# 02_-_MICROCONTROLADOR.net
KiCad netlist of a schematic drawn in Altium Designer
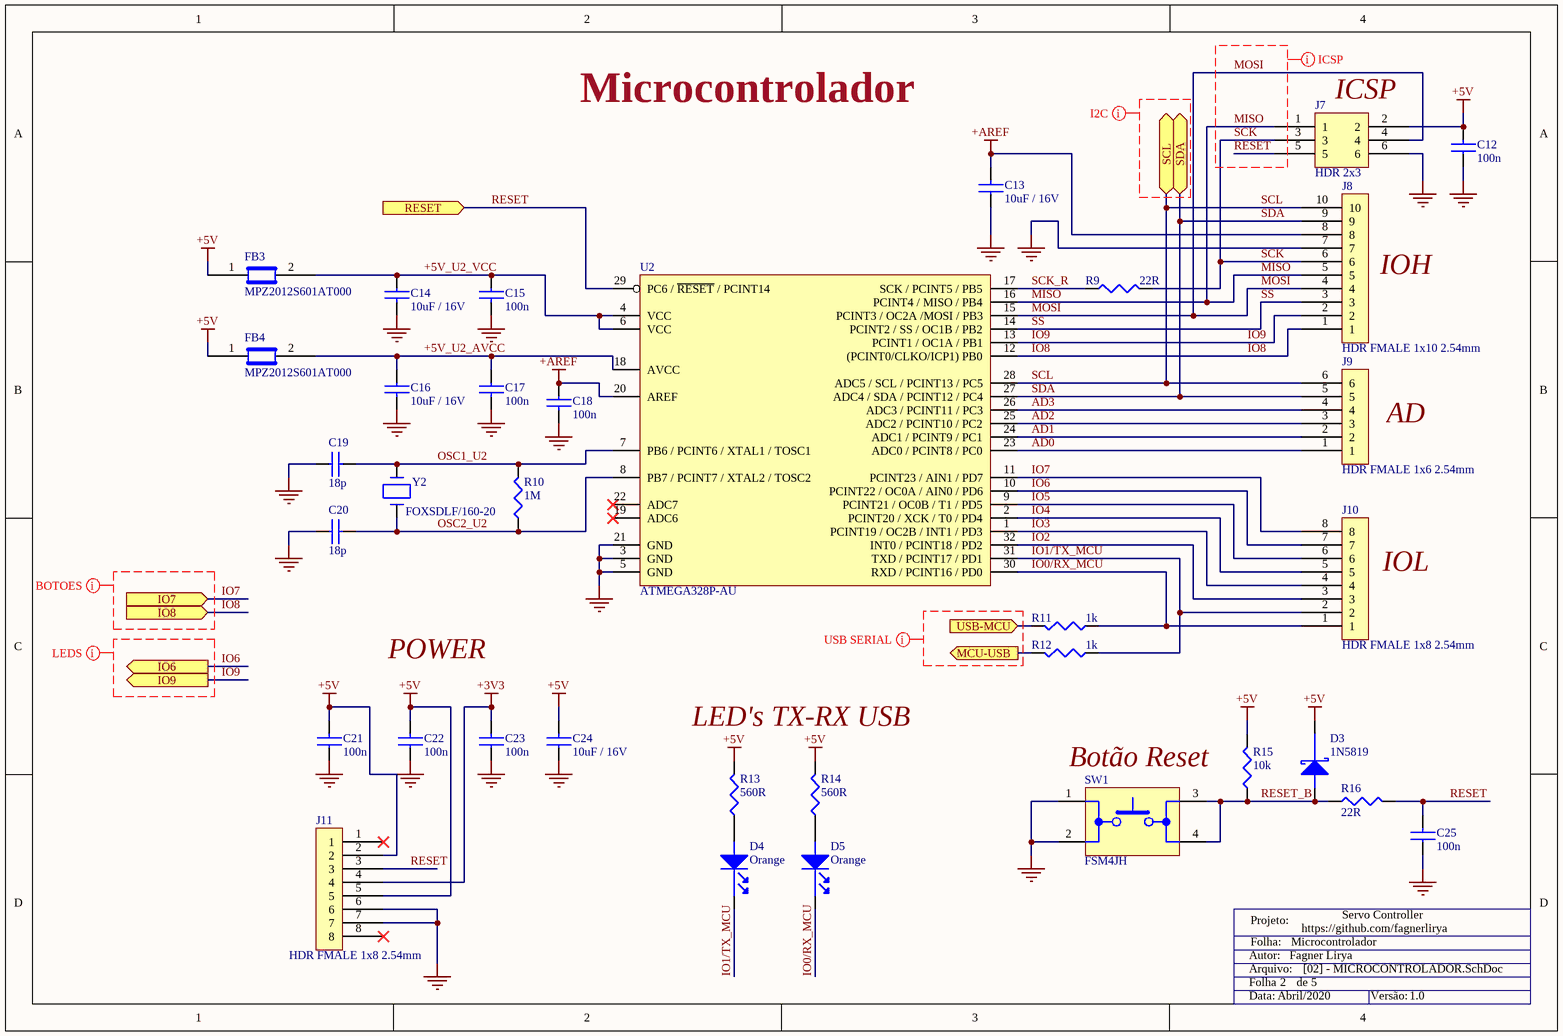
[diagram p0: [02] - MICROCONTROLADOR.SchDoc]

(export (version "E")
  (design (tool "Eeschema 10.0.6"))
  (components
    (comp (ref "C12")
      (value "100n")
      (footprint "C0805")
      (description "CAP CER 0.1UF 50V X7R 0805")
      (fields
        (field (name "MANUFACTURER") "TDK Corporation")
        (field (name "MANUFACTURER PART NUMBER") "C2012X7R1H104K085AA")
      )
      (libsource (lib "Servo_Control_Lib") (part "C2012X7R1H104K085AA_1"))
    )
    (comp (ref "C13")
      (value "10uF / 16V")
      (footprint "C0805")
      (description "CAP CER 10UF 16V X5R 0805")
      (fields
        (field (name "MANUFACTURER") "TDK Corporation")
        (field (name "MANUFACTURER PART NUMBER") "C2012X5R1C106M125AC")
      )
      (libsource (lib "Servo_Control_Lib") (part "C2012X5R1C106M125AC"))
    )
    (comp (ref "C14")
      (value "10uF / 16V")
      (footprint "C0805")
      (description "CAP CER 10UF 16V X5R 0805")
      (fields
        (field (name "MANUFACTURER") "TDK Corporation")
        (field (name "MANUFACTURER PART NUMBER") "C2012X5R1C106M125AC")
      )
      (libsource (lib "Servo_Control_Lib") (part "C2012X5R1C106M125AC"))
    )
    (comp (ref "C15")
      (value "100n")
      (footprint "C0805")
      (description "CAP CER 0.1UF 50V X7R 0805")
      (fields
        (field (name "MANUFACTURER") "TDK Corporation")
        (field (name "MANUFACTURER PART NUMBER") "C2012X7R1H104K085AA")
      )
      (libsource (lib "Servo_Control_Lib") (part "C2012X7R1H104K085AA_1"))
    )
    (comp (ref "C16")
      (value "10uF / 16V")
      (footprint "C0805")
      (description "CAP CER 10UF 16V X5R 0805")
      (fields
        (field (name "MANUFACTURER") "TDK Corporation")
        (field (name "MANUFACTURER PART NUMBER") "C2012X5R1C106M125AC")
      )
      (libsource (lib "Servo_Control_Lib") (part "C2012X5R1C106M125AC"))
    )
    (comp (ref "C17")
      (value "100n")
      (footprint "C0805")
      (description "CAP CER 0.1UF 50V X7R 0805")
      (fields
        (field (name "MANUFACTURER") "TDK Corporation")
        (field (name "MANUFACTURER PART NUMBER") "C2012X7R1H104K085AA")
      )
      (libsource (lib "Servo_Control_Lib") (part "C2012X7R1H104K085AA_1"))
    )
    (comp (ref "C18")
      (value "100n")
      (footprint "C0805")
      (description "CAP CER 0.1UF 50V X7R 0805")
      (fields
        (field (name "MANUFACTURER") "TDK Corporation")
        (field (name "MANUFACTURER PART NUMBER") "C2012X7R1H104K085AA")
      )
      (libsource (lib "Servo_Control_Lib") (part "C2012X7R1H104K085AA_1"))
    )
    (comp (ref "C19")
      (value "18p")
      (footprint "C0805")
      (description "CAP CER 18PF 50V NP0 0805")
      (fields
        (field (name "MANUFACTURER") "Kemet")
        (field (name "MANUFACTURER PART NUMBER") "C0805C180J5GACTU")
      )
      (libsource (lib "Servo_Control_Lib") (part "C0805C180J5GACTU"))
    )
    (comp (ref "C20")
      (value "18p")
      (footprint "C0805")
      (description "CAP CER 18PF 50V NP0 0805")
      (fields
        (field (name "MANUFACTURER") "Kemet")
        (field (name "MANUFACTURER PART NUMBER") "C0805C180J5GACTU")
      )
      (libsource (lib "Servo_Control_Lib") (part "C0805C180J5GACTU"))
    )
    (comp (ref "C21")
      (value "100n")
      (footprint "C0805")
      (description "CAP CER 0.1UF 50V X7R 0805")
      (fields
        (field (name "MANUFACTURER") "TDK Corporation")
        (field (name "MANUFACTURER PART NUMBER") "C2012X7R1H104K085AA")
      )
      (libsource (lib "Servo_Control_Lib") (part "C2012X7R1H104K085AA_1"))
    )
    (comp (ref "C22")
      (value "100n")
      (footprint "C0805")
      (description "CAP CER 0.1UF 50V X7R 0805")
      (fields
        (field (name "MANUFACTURER") "TDK Corporation")
        (field (name "MANUFACTURER PART NUMBER") "C2012X7R1H104K085AA")
      )
      (libsource (lib "Servo_Control_Lib") (part "C2012X7R1H104K085AA_1"))
    )
    (comp (ref "C23")
      (value "100n")
      (footprint "C0805")
      (description "CAP CER 0.1UF 50V X7R 0805")
      (fields
        (field (name "MANUFACTURER") "TDK Corporation")
        (field (name "MANUFACTURER PART NUMBER") "C2012X7R1H104K085AA")
      )
      (libsource (lib "Servo_Control_Lib") (part "C2012X7R1H104K085AA_1"))
    )
    (comp (ref "C24")
      (value "10uF / 16V")
      (footprint "C0805")
      (description "CAP CER 10UF 16V X5R 0805")
      (fields
        (field (name "MANUFACTURER") "TDK Corporation")
        (field (name "MANUFACTURER PART NUMBER") "C2012X5R1C106M125AC")
      )
      (libsource (lib "Servo_Control_Lib") (part "C2012X5R1C106M125AC"))
    )
    (comp (ref "C25")
      (value "100n")
      (footprint "C0805")
      (description "CAP CER 0.1UF 50V X7R 0805")
      (fields
        (field (name "MANUFACTURER") "TDK Corporation")
        (field (name "MANUFACTURER PART NUMBER") "C2012X7R1H104K085AA")
      )
      (libsource (lib "Servo_Control_Lib") (part "C2012X7R1H104K085AA_1"))
    )
    (comp (ref "D3")
      (value "1N5819")
      (footprint "1N5819")
      (description "Schottky Diodes & Rectifiers Schottky Barrier")
      (fields (field (name "MANUFACTURER") "ON Semiconductor / Fairchild"))
      (libsource (lib "Servo_Control_Lib") (part "1N5819"))
    )
    (comp (ref "D4")
      (value "Orange")
      (footprint "LED_0603")
      (description "LED ORANGE DIFFUSED 0603 SMD")
      (fields
        (field (name "MANUFACTURER") "OSRAM Opto Semiconductors Inc.")
        (field (name "MANUFACTURER PART NUMBER") "LO L29K-H2K1-24-Z")
      )
      (libsource (lib "Servo_Control_Lib") (part "LO L29K-H2K1-24-Z"))
    )
    (comp (ref "D5")
      (value "Orange")
      (footprint "LED_0603")
      (description "LED ORANGE DIFFUSED 0603 SMD")
      (fields
        (field (name "MANUFACTURER") "OSRAM Opto Semiconductors Inc.")
        (field (name "MANUFACTURER PART NUMBER") "LO L29K-H2K1-24-Z")
      )
      (libsource (lib "Servo_Control_Lib") (part "LO L29K-H2K1-24-Z"))
    )
    (comp (ref "FB3")
      (value "MPZ2012S601AT000")
      (footprint "C0805")
      (description "FERRITE CHIP BEAD 600 OHM SMD")
      (fields (field (name "MANUFACTURER") "TDK Corporation"))
      (libsource (lib "Servo_Control_Lib") (part "MPZ2012S601AT000"))
    )
    (comp (ref "FB4")
      (value "MPZ2012S601AT000")
      (footprint "C0805")
      (description "FERRITE CHIP BEAD 600 OHM SMD")
      (fields (field (name "MANUFACTURER") "TDK Corporation"))
      (libsource (lib "Servo_Control_Lib") (part "MPZ2012S601AT000"))
    )
    (comp (ref "J7")
      (value "HDR 2x3")
      (footprint "HDR_2x3_2.54MM")
      (description "CONN HEADER 6POS .100 STR 30AU")
      (fields (field (name "MANUFACTURER") "FCI") (field (name "MANUFACTURER PART NUMBER") "67997-106HLF"))
      (libsource (lib "Servo_Control_Lib") (part "67997-106HLF"))
    )
    (comp (ref "J8")
      (value "HDR FMALE 1x10 2.54mm")
      (footprint "Hdr_Female_1x10_2.54mm")
      (description "10-WAY SIL VERT SOCKET L/FREE")
      (fields
        (field (name "MANUFACTURER") "Harwin Inc.")
        (field (name "MANUFACTURER PART NUMBER") "M20-7821046")
      )
      (libsource (lib "Servo_Control_Lib") (part "M20-7821046"))
    )
    (comp (ref "J9")
      (value "HDR FMALE 1x6 2.54mm")
      (footprint "Hdr_Female_1x6_2.54mm")
      (description "06-WAY SIL VERT SOCKET L/FREE")
      (fields
        (field (name "MANUFACTURER") "Harwin Inc.")
        (field (name "MANUFACTURER PART NUMBER") "M20-7820646")
      )
      (libsource (lib "Servo_Control_Lib") (part "M20-7820646"))
    )
    (comp (ref "J10")
      (value "HDR FMALE 1x8 2.54mm")
      (footprint "Hdr_Female_1x8_2.54mm")
      (description "08-WAY SIL VERT SOCKET L/FREE")
      (fields
        (field (name "MANUFACTURER") "Harwin Inc.")
        (field (name "MANUFACTURER PART NUMBER") "M20-7820842")
      )
      (libsource (lib "Servo_Control_Lib") (part "M20-7820842"))
    )
    (comp (ref "J11")
      (value "HDR FMALE 1x8 2.54mm")
      (footprint "Hdr_Female_1x8_2.54mm")
      (description "08-WAY SIL VERT SOCKET L/FREE")
      (fields
        (field (name "MANUFACTURER") "Harwin Inc.")
        (field (name "MANUFACTURER PART NUMBER") "M20-7820842")
      )
      (libsource (lib "") (part "M20-7820842_1"))
    )
    (comp (ref "R9")
      (value "22R")
      (footprint "R0805")
      (description "RES SMD 22 OHM 1% 1/8W 0805")
      (fields
        (field (name "MANUFACTURER") "Yageo")
        (field (name "MANUFACTURER PART NUMBER") "RC0805FR-0722RL")
      )
      (libsource (lib "Servo_Control_Lib") (part "RC0805FR-0722RL"))
    )
    (comp (ref "R10")
      (value "1M")
      (footprint "R0805")
      (description "RES SMD 1M OHM 1% 1/8W 0805")
      (fields
        (field (name "MANUFACTURER") "Yageo")
        (field (name "MANUFACTURER PART NUMBER") "RC0805FR-071ML")
      )
      (libsource (lib "Servo_Control_Lib") (part "RC0805FR-071ML"))
    )
    (comp (ref "R11")
      (value "1k")
      (footprint "R0805")
      (description "RES SMD 1K OHM 1% 1/8W 0805")
      (fields
        (field (name "MANUFACTURER") "Yageo")
        (field (name "MANUFACTURER PART NUMBER") "RC0805FR-071KL")
      )
      (libsource (lib "Servo_Control_Lib") (part "RC0805FR-071KL"))
    )
    (comp (ref "R12")
      (value "1k")
      (footprint "R0805")
      (description "RES SMD 1K OHM 1% 1/8W 0805")
      (fields
        (field (name "MANUFACTURER") "Yageo")
        (field (name "MANUFACTURER PART NUMBER") "RC0805FR-071KL")
      )
      (libsource (lib "Servo_Control_Lib") (part "RC0805FR-071KL"))
    )
    (comp (ref "R13")
      (value "560R")
      (footprint "R0805")
      (description "RES SMD 560 OHM 1% 1/8W 0805")
      (fields
        (field (name "MANUFACTURER") "Yageo")
        (field (name "MANUFACTURER PART NUMBER") "RC0805FR-07560RL")
      )
      (libsource (lib "Servo_Control_Lib") (part "RC0805FR-07560RL"))
    )
    (comp (ref "R14")
      (value "560R")
      (footprint "R0805")
      (description "RES SMD 560 OHM 1% 1/8W 0805")
      (fields
        (field (name "MANUFACTURER") "Yageo")
        (field (name "MANUFACTURER PART NUMBER") "RC0805FR-07560RL")
      )
      (libsource (lib "Servo_Control_Lib") (part "RC0805FR-07560RL"))
    )
    (comp (ref "R15")
      (value "10k")
      (footprint "R0805")
      (description "RES SMD 10K OHM 1% 1/8W 0805")
      (fields
        (field (name "MANUFACTURER") "Yageo")
        (field (name "MANUFACTURER PART NUMBER") "RC0805FR-0710KL")
      )
      (libsource (lib "Servo_Control_Lib") (part "RC0805FR-0710KL"))
    )
    (comp (ref "R16")
      (value "22R")
      (footprint "R0805")
      (description "RES SMD 22 OHM 1% 1/8W 0805")
      (fields
        (field (name "MANUFACTURER") "Yageo")
        (field (name "MANUFACTURER PART NUMBER") "RC0805FR-0722RL")
      )
      (libsource (lib "Servo_Control_Lib") (part "RC0805FR-0722RL"))
    )
    (comp (ref "SW1")
      (value "FSM4JH")
      (footprint "FSM4JH")
      (description "Tactile Switches SPST OFF-(ON) Round pushbutton")
      (fields (field (name "MANUFACTURER") "TE Connectivity / Alcoswitch"))
      (libsource (lib "Servo_Control_Lib") (part "FSM4JH"))
    )
    (comp (ref "TitleBlock3")
      (value "Title Block")
      (libsource (lib "Servo_Control_Lib") (part "Title Block"))
    )
    (comp (ref "U2")
      (value "ATMEGA328P-AU")
      (footprint "TQFP32")
      (description "8-bit Microcontrollers - MCU 32KB In-system Flash 20MHz 1.8V-5.5V")
      (fields (field (name "MANUFACTURER") "Microchip Technology / Atmel"))
      (libsource (lib "Servo_Control_Lib") (part "ATMEGA328P-AU"))
    )
    (comp (ref "Y2")
      (value "FOXSDLF/160-20")
      (footprint "HC49SD")
      (description "Crystals 16MHz 20pF")
      (fields (field (name "MANUFACTURER") "Fox") (field (name "TOLERANCE") "50 PPM"))
      (libsource (lib "Servo_Control_Lib") (part "FOXSDLF/160-20"))
    )
  )
  (nets
    (net (code "1") (name "+3V3") (class "Default")
      (node (ref "C23") (pin "2") (pinfunction "2_2") (pintype "passive"))
      (node (ref "J11") (pin "4") (pinfunction "4_4") (pintype "passive"))
    )
    (net (code "2") (name "+5V") (class "Default")
      (node (ref "C12") (pin "2") (pinfunction "2_2") (pintype "passive"))
      (node (ref "C21") (pin "2") (pinfunction "2_2") (pintype "passive"))
      (node (ref "C22") (pin "2") (pinfunction "2_2") (pintype "passive"))
      (node (ref "C24") (pin "2") (pinfunction "2_2") (pintype "passive"))
      (node (ref "D3") (pin "1") (pinfunction "Cathode_1") (pintype "passive"))
      (node (ref "FB3") (pin "1") (pinfunction "1_1") (pintype "passive"))
      (node (ref "FB4") (pin "1") (pinfunction "1_1") (pintype "passive"))
      (node (ref "J11") (pin "2") (pinfunction "2_2") (pintype "passive"))
      (node (ref "J11") (pin "5") (pinfunction "5_5") (pintype "passive"))
      (node (ref "J7") (pin "2") (pinfunction "2_2") (pintype "passive"))
      (node (ref "R13") (pin "2") (pinfunction "2_2") (pintype "passive"))
      (node (ref "R14") (pin "2") (pinfunction "2_2") (pintype "passive"))
      (node (ref "R15") (pin "2") (pinfunction "2_2") (pintype "passive"))
    )
    (net (code "3") (name "+AREF") (class "Default")
      (node (ref "C13") (pin "2") (pinfunction "2_2") (pintype "passive"))
      (node (ref "C18") (pin "1") (pinfunction "1_1") (pintype "passive"))
      (node (ref "J8") (pin "8") (pinfunction "8_8") (pintype "passive"))
      (node (ref "U2") (pin "20") (pinfunction "AREF_20") (pintype "passive"))
    )
    (net (code "4") (name "/+5V_U2_AVCC") (class "Default")
      (node (ref "C16") (pin "1") (pinfunction "1_1") (pintype "passive"))
      (node (ref "C17") (pin "1") (pinfunction "1_1") (pintype "passive"))
      (node (ref "FB4") (pin "2") (pinfunction "2_2") (pintype "passive"))
      (node (ref "U2") (pin "18") (pinfunction "AVCC_18") (pintype "passive"))
    )
    (net (code "5") (name "/+5V_U2_VCC") (class "Default")
      (node (ref "C14") (pin "1") (pinfunction "1_1") (pintype "passive"))
      (node (ref "C15") (pin "1") (pinfunction "1_1") (pintype "passive"))
      (node (ref "FB3") (pin "2") (pinfunction "2_2") (pintype "passive"))
      (node (ref "U2") (pin "4") (pinfunction "VCC_4") (pintype "passive"))
      (node (ref "U2") (pin "6") (pinfunction "VCC_6") (pintype "passive"))
    )
    (net (code "6") (name "/AD0") (class "Default")
      (node (ref "J9") (pin "1") (pinfunction "1_1") (pintype "passive"))
      (node (ref "U2") (pin "23") (pinfunction "ADC0_/_PCINT8_/_PC0_23") (pintype "passive"))
    )
    (net (code "7") (name "/AD1") (class "Default")
      (node (ref "J9") (pin "2") (pinfunction "2_2") (pintype "passive"))
      (node (ref "U2") (pin "24") (pinfunction "ADC1_/_PCINT9_/_PC1_24") (pintype "passive"))
    )
    (net (code "8") (name "/AD2") (class "Default")
      (node (ref "J9") (pin "3") (pinfunction "3_3") (pintype "passive"))
      (node (ref "U2") (pin "25") (pinfunction "ADC2_/_PCINT10_/_PC2_25") (pintype "passive"))
    )
    (net (code "9") (name "/AD3") (class "Default")
      (node (ref "J9") (pin "4") (pinfunction "4_4") (pintype "passive"))
      (node (ref "U2") (pin "26") (pinfunction "ADC3_/_PCINT11_/_PC3_26") (pintype "passive"))
    )
    (net (code "10") (name "/IO0{slash}RX_MCU") (class "Default")
      (node (ref "D5") (pin "1") (pinfunction "Cathode_1") (pintype "passive"))
      (node (ref "J10") (pin "1") (pinfunction "1_1") (pintype "passive"))
      (node (ref "R11") (pin "1") (pinfunction "1_1") (pintype "passive"))
      (node (ref "U2") (pin "30") (pinfunction "RXD_/_PCINT16_/_PD0_30") (pintype "passive"))
    )
    (net (code "11") (name "/IO1{slash}TX_MCU") (class "Default")
      (node (ref "D4") (pin "1") (pinfunction "Cathode_1") (pintype "passive"))
      (node (ref "J10") (pin "2") (pinfunction "2_2") (pintype "passive"))
      (node (ref "R12") (pin "1") (pinfunction "1_1") (pintype "passive"))
      (node (ref "U2") (pin "31") (pinfunction "TXD_/_PCINT17_/_PD1_31") (pintype "passive"))
    )
    (net (code "12") (name "/IO2") (class "Default")
      (node (ref "J10") (pin "3") (pinfunction "3_3") (pintype "passive"))
      (node (ref "U2") (pin "32") (pinfunction "INT0_/_PCINT18_/_PD2_32") (pintype "passive"))
    )
    (net (code "13") (name "/IO3") (class "Default")
      (node (ref "J10") (pin "4") (pinfunction "4_4") (pintype "passive"))
      (node (ref "U2") (pin "1") (pinfunction "PCINT19_/_OC2B_/_INT1_/_PD3_1") (pintype "passive"))
    )
    (net (code "14") (name "/IO4") (class "Default")
      (node (ref "J10") (pin "5") (pinfunction "5_5") (pintype "passive"))
      (node (ref "U2") (pin "2") (pinfunction "PCINT20_/_XCK_/_T0_/_PD4_2") (pintype "passive"))
    )
    (net (code "15") (name "/IO5") (class "Default")
      (node (ref "J10") (pin "6") (pinfunction "6_6") (pintype "passive"))
      (node (ref "U2") (pin "9") (pinfunction "PCINT21_/_OC0B_/_T1_/_PD5_9") (pintype "passive"))
    )
    (net (code "16") (name "/IO6") (class "Default")
      (node (ref "J10") (pin "7") (pinfunction "7_7") (pintype "passive"))
      (node (ref "U2") (pin "10") (pinfunction "PCINT22_/_OC0A_/_AIN0_/_PD6_10") (pintype "passive"))
    )
    (net (code "17") (name "/IO7") (class "Default")
      (node (ref "J10") (pin "8") (pinfunction "8_8") (pintype "passive"))
      (node (ref "U2") (pin "11") (pinfunction "PCINT23_/_AIN1_/_PD7_11") (pintype "passive"))
    )
    (net (code "18") (name "/IO8") (class "Default")
      (node (ref "J8") (pin "1") (pinfunction "1_1") (pintype "passive"))
      (node (ref "U2") (pin "12") (pinfunction "(PCINT0/CLKO/ICP1)_PB0_12") (pintype "passive"))
    )
    (net (code "19") (name "/IO9") (class "Default")
      (node (ref "J8") (pin "2") (pinfunction "2_2") (pintype "passive"))
      (node (ref "U2") (pin "13") (pinfunction "PCINT1_/_OC1A_/_PB1_13") (pintype "passive"))
    )
    (net (code "20") (name "/MCU-USB") (class "Default")
      (node (ref "R12") (pin "2") (pinfunction "2_2") (pintype "passive"))
    )
    (net (code "21") (name "/MISO") (class "Default")
      (node (ref "J7") (pin "1") (pinfunction "1_1") (pintype "passive"))
      (node (ref "J8") (pin "5") (pinfunction "5_5") (pintype "passive"))
      (node (ref "U2") (pin "16") (pinfunction "PCINT4_/_MISO_/_PB4_16") (pintype "passive"))
    )
    (net (code "22") (name "/MOSI") (class "Default")
      (node (ref "J7") (pin "4") (pinfunction "4_4") (pintype "passive"))
      (node (ref "J8") (pin "4") (pinfunction "4_4") (pintype "passive"))
      (node (ref "U2") (pin "15") (pinfunction "PCINT3_/_OC2A_/MOSI_/_PB3_15") (pintype "passive"))
    )
    (net (code "23") (name "/OSC1_U2") (class "Default")
      (node (ref "C19") (pin "2") (pinfunction "2_2") (pintype "passive"))
      (node (ref "R10") (pin "2") (pinfunction "2_2") (pintype "passive"))
      (node (ref "U2") (pin "7") (pinfunction "PB6_/_PCINT6_/_XTAL1_/_TOSC1_7") (pintype "passive"))
      (node (ref "Y2") (pin "2") (pinfunction "2_2") (pintype "passive"))
    )
    (net (code "24") (name "/OSC2_U2") (class "Default")
      (node (ref "C20") (pin "2") (pinfunction "2_2") (pintype "passive"))
      (node (ref "R10") (pin "1") (pinfunction "1_1") (pintype "passive"))
      (node (ref "U2") (pin "8") (pinfunction "PB7_/_PCINT7_/_XTAL2_/_TOSC2_8") (pintype "passive"))
      (node (ref "Y2") (pin "1") (pinfunction "1_1") (pintype "passive"))
    )
    (net (code "25") (name "/RESET") (class "Default")
      (node (ref "C25") (pin "2") (pinfunction "2_2") (pintype "passive"))
      (node (ref "J11") (pin "3") (pinfunction "3_3") (pintype "passive"))
      (node (ref "J7") (pin "5") (pinfunction "5_5") (pintype "passive"))
      (node (ref "R16") (pin "2") (pinfunction "2_2") (pintype "passive"))
      (node (ref "U2") (pin "29") (pinfunction "PC6_/_~{RESET}_/_PCINT14_29") (pintype "passive"))
    )
    (net (code "26") (name "/RESET_B") (class "Default")
      (node (ref "D3") (pin "2") (pinfunction "Anode_2") (pintype "passive"))
      (node (ref "R15") (pin "1") (pinfunction "1_1") (pintype "passive"))
      (node (ref "R16") (pin "1") (pinfunction "1_1") (pintype "passive"))
      (node (ref "SW1") (pin "3") (pinfunction "3_3") (pintype "passive"))
      (node (ref "SW1") (pin "4") (pinfunction "4_4") (pintype "passive"))
    )
    (net (code "27") (name "/SCK") (class "Default")
      (node (ref "J7") (pin "3") (pinfunction "3_3") (pintype "passive"))
      (node (ref "J8") (pin "6") (pinfunction "6_6") (pintype "passive"))
      (node (ref "R9") (pin "2") (pinfunction "2_2") (pintype "passive"))
    )
    (net (code "28") (name "/SCK_R") (class "Default")
      (node (ref "R9") (pin "1") (pinfunction "1_1") (pintype "passive"))
      (node (ref "U2") (pin "17") (pinfunction "SCK_/_PCINT5_/_PB5_17") (pintype "passive"))
    )
    (net (code "29") (name "/SCL") (class "Default")
      (node (ref "J8") (pin "10") (pinfunction "10_10") (pintype "passive"))
      (node (ref "J9") (pin "6") (pinfunction "6_6") (pintype "passive"))
      (node (ref "U2") (pin "28") (pinfunction "ADC5_/_SCL_/_PCINT13_/_PC5_28") (pintype "passive"))
    )
    (net (code "30") (name "/SDA") (class "Default")
      (node (ref "J8") (pin "9") (pinfunction "9_9") (pintype "passive"))
      (node (ref "J9") (pin "5") (pinfunction "5_5") (pintype "passive"))
      (node (ref "U2") (pin "27") (pinfunction "ADC4_/_SDA_/_PCINT12_/_PC4_27") (pintype "passive"))
    )
    (net (code "31") (name "/SS") (class "Default")
      (node (ref "J8") (pin "3") (pinfunction "3_3") (pintype "passive"))
      (node (ref "U2") (pin "14") (pinfunction "PCINT2_/_SS_/_OC1B_/_PB2_14") (pintype "passive"))
    )
    (net (code "32") (name "/USB-MCU") (class "Default")
      (node (ref "R11") (pin "2") (pinfunction "2_2") (pintype "passive"))
    )
    (net (code "33") (name "GND") (class "Default")
      (node (ref "C12") (pin "1") (pinfunction "1_1") (pintype "passive"))
      (node (ref "C13") (pin "1") (pinfunction "1_1") (pintype "passive"))
      (node (ref "C14") (pin "2") (pinfunction "2_2") (pintype "passive"))
      (node (ref "C15") (pin "2") (pinfunction "2_2") (pintype "passive"))
      (node (ref "C16") (pin "2") (pinfunction "2_2") (pintype "passive"))
      (node (ref "C17") (pin "2") (pinfunction "2_2") (pintype "passive"))
      (node (ref "C18") (pin "2") (pinfunction "2_2") (pintype "passive"))
      (node (ref "C19") (pin "1") (pinfunction "1_1") (pintype "passive"))
      (node (ref "C20") (pin "1") (pinfunction "1_1") (pintype "passive"))
      (node (ref "C21") (pin "1") (pinfunction "1_1") (pintype "passive"))
      (node (ref "C22") (pin "1") (pinfunction "1_1") (pintype "passive"))
      (node (ref "C23") (pin "1") (pinfunction "1_1") (pintype "passive"))
      (node (ref "C24") (pin "1") (pinfunction "1_1") (pintype "passive"))
      (node (ref "C25") (pin "1") (pinfunction "1_1") (pintype "passive"))
      (node (ref "J11") (pin "6") (pinfunction "6_6") (pintype "passive"))
      (node (ref "J11") (pin "7") (pinfunction "7_7") (pintype "passive"))
      (node (ref "J7") (pin "6") (pinfunction "6_6") (pintype "passive"))
      (node (ref "J8") (pin "7") (pinfunction "7_7") (pintype "passive"))
      (node (ref "SW1") (pin "1") (pinfunction "1_1") (pintype "passive"))
      (node (ref "SW1") (pin "2") (pinfunction "2_2") (pintype "passive"))
      (node (ref "U2") (pin "21") (pinfunction "GND_21") (pintype "passive"))
      (node (ref "U2") (pin "3") (pinfunction "GND_3") (pintype "passive"))
      (node (ref "U2") (pin "5") (pinfunction "GND_5") (pintype "passive"))
    )
    (net (code "34") (name "Net-(D4-Anode)") (class "Default")
      (node (ref "D4") (pin "2") (pinfunction "Anode_2") (pintype "passive"))
      (node (ref "R13") (pin "1") (pinfunction "1_1") (pintype "passive"))
    )
    (net (code "35") (name "Net-(D5-Anode)") (class "Default")
      (node (ref "D5") (pin "2") (pinfunction "Anode_2") (pintype "passive"))
      (node (ref "R14") (pin "1") (pinfunction "1_1") (pintype "passive"))
    )
    (net (code "36") (name "unconnected-(J11-Pad1)") (class "Default")
      (node (ref "J11") (pin "1") (pinfunction "1_1") (pintype "passive+no_connect"))
    )
    (net (code "37") (name "unconnected-(J11-Pad8)") (class "Default")
      (node (ref "J11") (pin "8") (pinfunction "8_8") (pintype "passive+no_connect"))
    )
    (net (code "38") (name "unconnected-(U2-ADC6-Pad19)") (class "Default")
      (node (ref "U2") (pin "19") (pinfunction "ADC6_19") (pintype "passive+no_connect"))
    )
    (net (code "39") (name "unconnected-(U2-ADC7-Pad22)") (class "Default")
      (node (ref "U2") (pin "22") (pinfunction "ADC7_22") (pintype "passive+no_connect"))
    )
  )
)
